# UART_TO_USB_LOG.net
KiCad netlist of a schematic drawn in Altium Designer
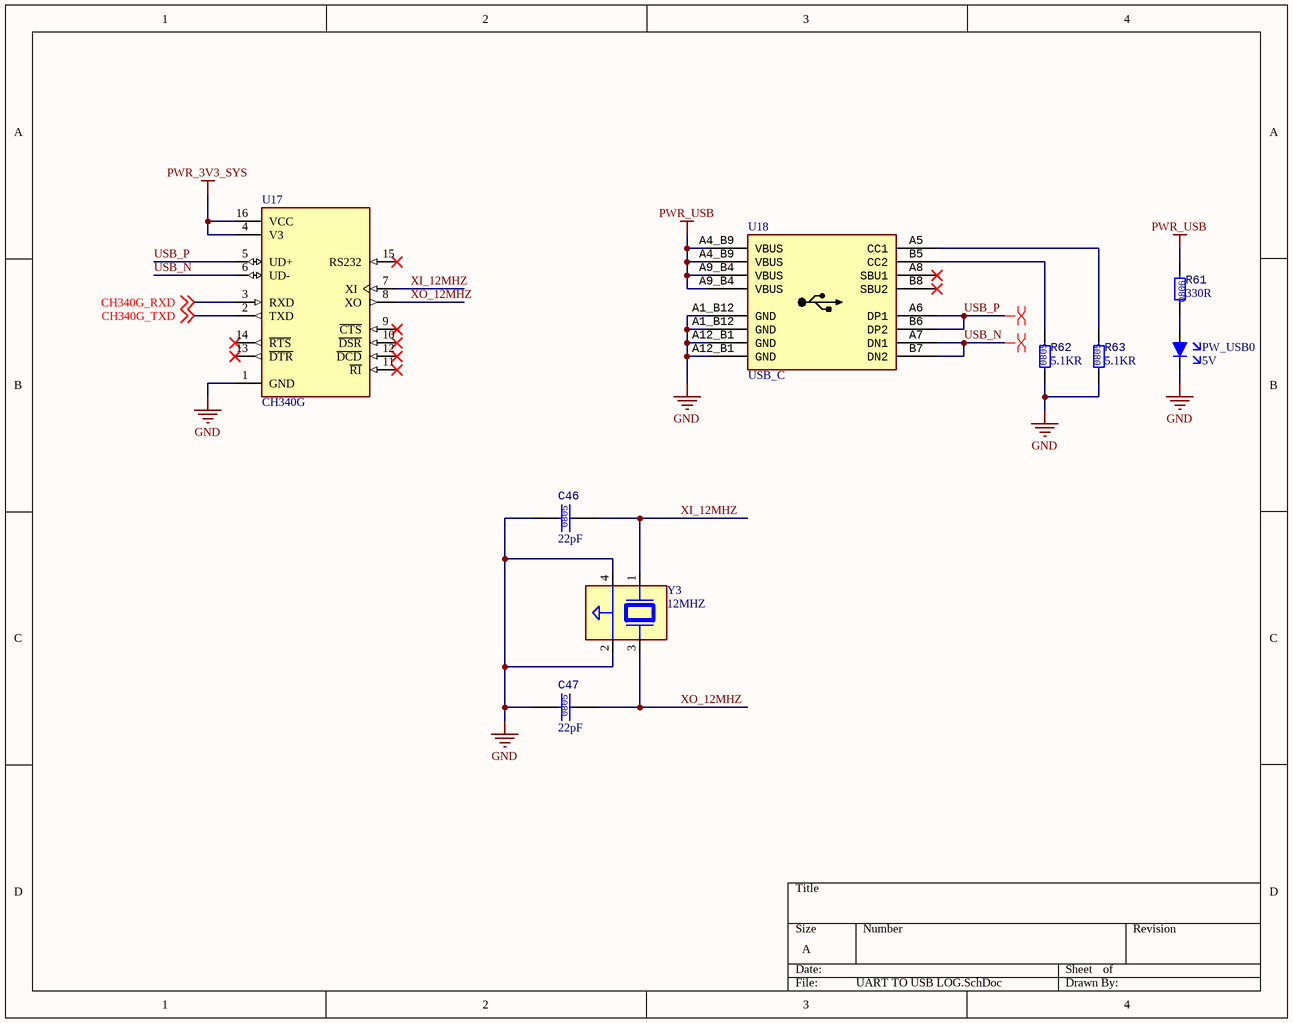
[diagram p0: UART TO USB LOG.SchDoc]

(export (version "E")
  (design (tool "Eeschema 10.0.6"))
  (components
    (comp (ref "C46")
      (value "22pF")
      (footprint "CAPCER 0805 SMD")
      (description "CAPACITOR SMD 22pF 50V 10% 0805")
      (fields (field (name "SIZE") "0805") (field (name "TOLERANCE") "10%"))
      (libsource (lib "Database_Libs1") (part "CAPACITOR"))
    )
    (comp (ref "C47")
      (value "22pF")
      (footprint "CAPCER 0805 SMD")
      (description "CAPACITOR SMD 22pF 50V 10% 0805")
      (fields (field (name "SIZE") "0805") (field (name "TOLERANCE") "10%"))
      (libsource (lib "Database_Libs1") (part "CAPACITOR"))
    )
    (comp (ref "PW_USB0")
      (value "5V")
      (footprint "LED 0805 SMD")
      (description "Size 2x1.2mm, điện áp 1.8-2.6VDC")
      (fields (field (name "Comment") "LED_RED"))
      (libsource (lib "Database_Libs1") (part "LED_RED"))
    )
    (comp (ref "R61")
      (value "330R")
      (footprint "RESC 0805 SMD")
      (description "RESISTOR SMD 330R OHM 1% 125mW 0805")
      (fields (field (name "SIZE") "0806") (field (name "TOLERANCE") "1%"))
      (libsource (lib "Database_Libs1") (part "RESISTOR"))
    )
    (comp (ref "R62")
      (value "5.1KR")
      (footprint "RESC 0805 SMD")
      (fields (field (name "SIZE") "0805"))
      (libsource (lib "Database_Libs2") (part "RESISTOR"))
    )
    (comp (ref "R63")
      (value "5.1KR")
      (footprint "RESC 0805 SMD")
      (fields (field (name "SIZE") "0805"))
      (libsource (lib "Database_Libs2") (part "RESISTOR"))
    )
    (comp (ref "U17")
      (value "CH340G")
      (footprint "SOP-16")
      (libsource (lib "Database_Libs1") (part "CH340G"))
    )
    (comp (ref "U18")
      (value "USB_C")
      (footprint "TYPEC-16POS")
      (fields (field (name "Comment") "USB_TYPE_C"))
      (libsource (lib "Database_Libs1") (part "USB_C"))
    )
    (comp (ref "Y3")
      (value "12MHZ")
      (footprint "XTAL_5032")
      (fields (field (name "Comment") "XTAL_12Mhz"))
      (libsource (lib "Database_Libs2") (part "XTAL_12MHZ"))
    )
  )
  (nets
    (net (code "2") (name "/USB_N") (class "Default")
      (node (ref "U17") (pin "6") (pinfunction "UD-_6") (pintype "bidirectional"))
      (node (ref "U18") (pin "A7") (pinfunction "DN1_A7") (pintype "passive"))
      (node (ref "U18") (pin "B7") (pinfunction "DN2_B7") (pintype "passive"))
    )
    (net (code "3") (name "/USB_P") (class "Default")
      (node (ref "U17") (pin "5") (pinfunction "UD+_5") (pintype "bidirectional"))
      (node (ref "U18") (pin "A6") (pinfunction "DP1_A6") (pintype "passive"))
      (node (ref "U18") (pin "B6") (pinfunction "DP2_B6") (pintype "passive"))
    )
    (net (code "4") (name "/XI_12MHZ") (class "Default")
      (node (ref "C46") (pin "2") (pinfunction "2_2") (pintype "passive"))
      (node (ref "U17") (pin "7") (pinfunction "XI_7") (pintype "input"))
      (node (ref "Y3") (pin "1") (pinfunction "1_1") (pintype "passive"))
    )
    (net (code "5") (name "/XO_12MHZ") (class "Default")
      (node (ref "C47") (pin "2") (pinfunction "2_2") (pintype "passive"))
      (node (ref "U17") (pin "8") (pinfunction "XO_8") (pintype "output"))
      (node (ref "Y3") (pin "3") (pinfunction "2_3") (pintype "passive"))
    )
    (net (code "6") (name "CH340G_RXD") (class "Default")
      (node (ref "U17") (pin "3") (pinfunction "RXD_3") (pintype "input"))
    )
    (net (code "7") (name "CH340G_TXD") (class "Default")
      (node (ref "U17") (pin "2") (pinfunction "TXD_2") (pintype "output"))
    )
    (net (code "8") (name "GND") (class "Default")
      (node (ref "C46") (pin "1") (pinfunction "1_1") (pintype "passive"))
      (node (ref "C47") (pin "1") (pinfunction "1_1") (pintype "passive"))
      (node (ref "PW_USB0") (pin "C") (pinfunction "K_C") (pintype "passive"))
      (node (ref "R62") (pin "1") (pinfunction "1_1") (pintype "passive"))
      (node (ref "R63") (pin "1") (pinfunction "1_1") (pintype "passive"))
      (node (ref "U17") (pin "1") (pinfunction "GND_1") (pintype "power_in"))
      (node (ref "U18") (pin "A12_B1") (pinfunction "GND_A12_B1") (pintype "passive"))
      (node (ref "U18") (pin "A1_B12") (pinfunction "GND_A1_B12") (pintype "passive"))
      (node (ref "Y3") (pin "2") (pinfunction "GND_2") (pintype "power_in"))
      (node (ref "Y3") (pin "4") (pinfunction "GND_4") (pintype "passive"))
    )
    (net (code "9") (name "Net-(PW_USB0-PadA)") (class "Default")
      (node (ref "PW_USB0") (pin "A") (pinfunction "A_A") (pintype "passive"))
      (node (ref "R61") (pin "2") (pinfunction "2_2") (pintype "passive"))
    )
    (net (code "10") (name "Net-(U18-CC1)") (class "Default")
      (node (ref "R63") (pin "2") (pinfunction "2_2") (pintype "passive"))
      (node (ref "U18") (pin "A5") (pinfunction "CC1_A5") (pintype "passive"))
    )
    (net (code "11") (name "Net-(U18-CC2)") (class "Default")
      (node (ref "R62") (pin "2") (pinfunction "2_2") (pintype "passive"))
      (node (ref "U18") (pin "B5") (pinfunction "CC2_B5") (pintype "passive"))
    )
    (net (code "12") (name "PWR_3V3_SYS") (class "Default")
      (node (ref "U17") (pin "16") (pinfunction "VCC_16") (pintype "power_in"))
      (node (ref "U17") (pin "4") (pinfunction "V3_4") (pintype "power_in"))
    )
    (net (code "13") (name "PWR_USB") (class "Default")
      (node (ref "R61") (pin "1") (pinfunction "1_1") (pintype "passive"))
      (node (ref "U18") (pin "A4_B9") (pinfunction "VBUS_A4_B9") (pintype "passive"))
      (node (ref "U18") (pin "A9_B4") (pinfunction "VBUS_A9_B4") (pintype "passive"))
    )
    (net (code "14") (name "unconnected-(U17-RS232-Pad15)") (class "Default")
      (node (ref "U17") (pin "15") (pinfunction "RS232_15") (pintype "input+no_connect"))
    )
    (net (code "15") (name "unconnected-(U17-~{CTS}-Pad9)") (class "Default")
      (node (ref "U17") (pin "9") (pinfunction "~{CTS}_9") (pintype "input+no_connect"))
    )
    (net (code "16") (name "unconnected-(U17-~{DCD}-Pad12)") (class "Default")
      (node (ref "U17") (pin "12") (pinfunction "~{DCD}_12") (pintype "input+no_connect"))
    )
    (net (code "17") (name "unconnected-(U17-~{DSR}-Pad10)") (class "Default")
      (node (ref "U17") (pin "10") (pinfunction "~{DSR}_10") (pintype "input+no_connect"))
    )
    (net (code "18") (name "unconnected-(U17-~{DTR}-Pad13)") (class "Default")
      (node (ref "U17") (pin "13") (pinfunction "~{DTR}_13") (pintype "output+no_connect"))
    )
    (net (code "19") (name "unconnected-(U17-~{RI}-Pad11)") (class "Default")
      (node (ref "U17") (pin "11") (pinfunction "~{RI}_11") (pintype "input+no_connect"))
    )
    (net (code "20") (name "unconnected-(U17-~{RTS}-Pad14)") (class "Default")
      (node (ref "U17") (pin "14") (pinfunction "~{RTS}_14") (pintype "output+no_connect"))
    )
    (net (code "21") (name "unconnected-(U18-SBU1-PadA8)") (class "Default")
      (node (ref "U18") (pin "A8") (pinfunction "SBU1_A8") (pintype "passive+no_connect"))
    )
    (net (code "22") (name "unconnected-(U18-SBU2-PadB8)") (class "Default")
      (node (ref "U18") (pin "B8") (pinfunction "SBU2_B8") (pintype "passive+no_connect"))
    )
  )
)
